# Pure_VCA.net
KiCad netlist of a schematic drawn in EAGLE
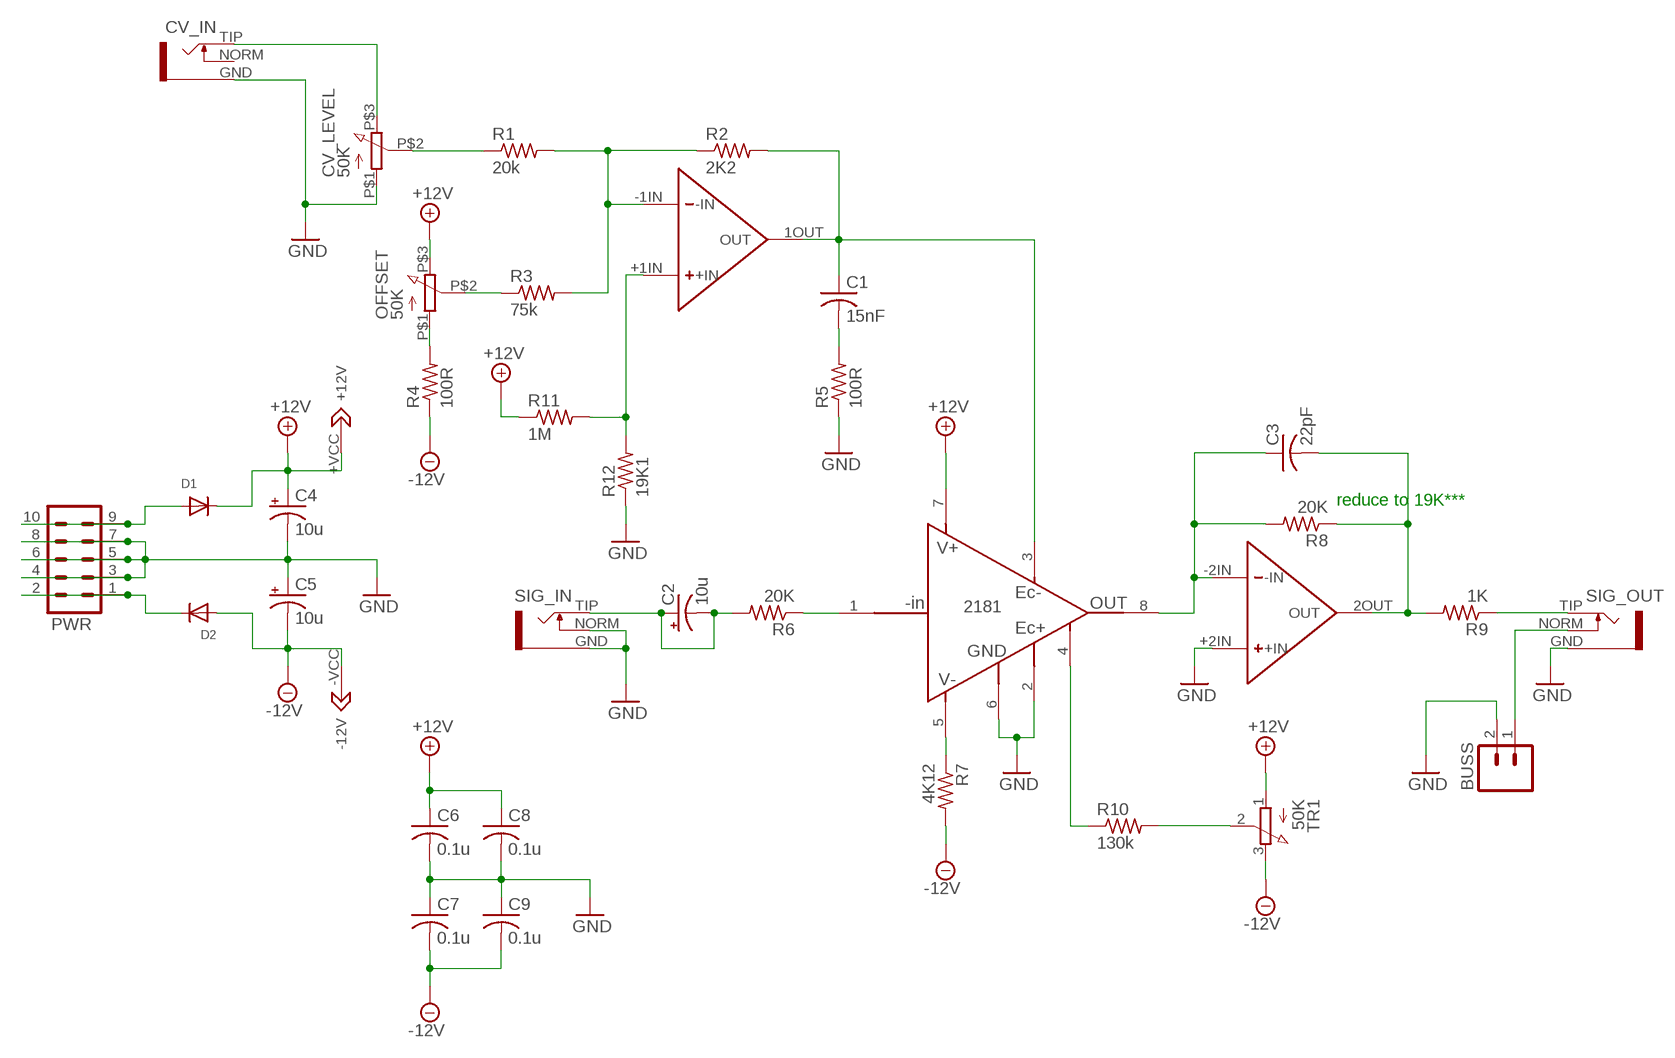
[diagram p0: schematic, sheet 1]

(export (version "E")
  (design (tool "Eeschema 10.0.6"))
  (components
    (comp (ref "BUSS")
      (value "M02PTH")
      (footprint "eagle-import:1X02")
      (libsource (lib "eagle-import") (part "M02PTH"))
    )
    (comp (ref "C1")
      (value "15nF")
      (footprint "eagle-import:C0805K")
      (libsource (lib "eagle-import") (part "C-USC0805K"))
    )
    (comp (ref "C2")
      (value "10u")
      (footprint "eagle-import:153CLV-0505")
      (libsource (lib "eagle-import") (part "CPOL-US153CLV-0505"))
    )
    (comp (ref "C3")
      (value "22pF")
      (footprint "eagle-import:C0805K")
      (libsource (lib "eagle-import") (part "C-USC0805K"))
    )
    (comp (ref "C4")
      (value "10u")
      (footprint "eagle-import:153CLV-0505")
      (libsource (lib "eagle-import") (part "CPOL-US153CLV-0505"))
    )
    (comp (ref "C5")
      (value "10u")
      (footprint "eagle-import:153CLV-0505")
      (libsource (lib "eagle-import") (part "CPOL-US153CLV-0505"))
    )
    (comp (ref "C6")
      (value "0.1u")
      (footprint "eagle-import:C0805K")
      (libsource (lib "eagle-import") (part "C-USC0805K"))
    )
    (comp (ref "C7")
      (value "0.1u")
      (footprint "eagle-import:C0805K")
      (libsource (lib "eagle-import") (part "C-USC0805K"))
    )
    (comp (ref "C8")
      (value "0.1u")
      (footprint "eagle-import:C0805K")
      (libsource (lib "eagle-import") (part "C-USC0805K"))
    )
    (comp (ref "C9")
      (value "0.1u")
      (footprint "eagle-import:C0805K")
      (libsource (lib "eagle-import") (part "C-USC0805K"))
    )
    (comp (ref "CV_IN")
      (value "S_JACK")
      (footprint "eagle-import:S_JACK")
      (libsource (lib "eagle-import") (part "S_JACK"))
    )
    (comp (ref "CV_LEVEL")
      (value "50K")
      (footprint "eagle-import:Q-POT")
      (libsource (lib "eagle-import") (part "Q-POT"))
    )
    (comp (ref "D1")
      (value "DIODESMA")
      (footprint "eagle-import:SMADIODE")
      (libsource (lib "eagle-import") (part "DIODESMA"))
    )
    (comp (ref "D2")
      (value "DIODESMA")
      (footprint "eagle-import:SMADIODE")
      (libsource (lib "eagle-import") (part "DIODESMA"))
    )
    (comp (ref "OFFSET")
      (value "50K")
      (footprint "eagle-import:Q-POT")
      (libsource (lib "eagle-import") (part "Q-POT"))
    )
    (comp (ref "PWR")
      (value "M05X2SHD")
      (footprint "eagle-import:2X5-SHROUDED")
      (libsource (lib "eagle-import") (part "M05X2SHD"))
    )
    (comp (ref "R1")
      (value "20k")
      (footprint "eagle-import:R0805")
      (libsource (lib "eagle-import") (part "R-US_R0805"))
    )
    (comp (ref "R2")
      (value "2K2")
      (footprint "eagle-import:R0805")
      (libsource (lib "eagle-import") (part "R-US_R0805"))
    )
    (comp (ref "R3")
      (value "75k")
      (footprint "eagle-import:R0805")
      (libsource (lib "eagle-import") (part "R-US_R0805"))
    )
    (comp (ref "R4")
      (value "100R")
      (footprint "eagle-import:R0805")
      (libsource (lib "eagle-import") (part "R-US_R0805"))
    )
    (comp (ref "R5")
      (value "100R")
      (footprint "eagle-import:R0805")
      (libsource (lib "eagle-import") (part "R-US_R0805"))
    )
    (comp (ref "R6")
      (value "20K")
      (footprint "eagle-import:R0805")
      (libsource (lib "eagle-import") (part "R-US_R0805"))
    )
    (comp (ref "R7")
      (value "4K12")
      (footprint "eagle-import:R0805")
      (libsource (lib "eagle-import") (part "R-US_R0805"))
    )
    (comp (ref "R8")
      (value "20K")
      (footprint "eagle-import:R0805")
      (libsource (lib "eagle-import") (part "R-US_R0805"))
    )
    (comp (ref "R9")
      (value "1K")
      (footprint "eagle-import:R0805")
      (libsource (lib "eagle-import") (part "R-US_R0805"))
    )
    (comp (ref "R10")
      (value "130k")
      (footprint "eagle-import:R0805")
      (libsource (lib "eagle-import") (part "R-US_R0805"))
    )
    (comp (ref "R11")
      (value "1M")
      (footprint "eagle-import:R0805")
      (libsource (lib "eagle-import") (part "R-US_R0805"))
    )
    (comp (ref "R12")
      (value "19K1")
      (footprint "eagle-import:R0805")
      (libsource (lib "eagle-import") (part "R-US_R0805"))
    )
    (comp (ref "SIG_IN")
      (value "S_JACK")
      (footprint "eagle-import:S_JACK")
      (libsource (lib "eagle-import") (part "S_JACK"))
    )
    (comp (ref "SIG_OUT")
      (value "S_JACK")
      (footprint "eagle-import:S_JACK")
      (libsource (lib "eagle-import") (part "S_JACK"))
    )
    (comp (ref "TR1")
      (value "50K")
      (footprint "eagle-import:TRIM_3269W")
      (libsource (lib "eagle-import") (part "TRIM_3269W"))
    )
    (comp (ref "U1")
      (value "DUAL_OPAMP")
      (footprint "eagle-import:DUAL_OPAMP")
      (libsource (lib "eagle-import") (part "DUAL_OPAMP"))
    )
    (comp (ref "U2")
      (value "THAT_2181_SMD")
      (footprint "eagle-import:SOIC--8")
      (libsource (lib "eagle-import") (part "THAT_2181_SMD"))
    )
  )
  (nets
    (net (code "1") (name "+12V") (class "Default")
      (node (ref "C4") (pin "+") (pinfunction "+_+") (pintype "passive"))
      (node (ref "C6") (pin "1") (pinfunction "1_1") (pintype "passive"))
      (node (ref "C8") (pin "1") (pinfunction "1_1") (pintype "passive"))
      (node (ref "D1") (pin "C") (pinfunction "C_C") (pintype "passive"))
      (node (ref "OFFSET") (pin "P$3") (pinfunction "3_P$3") (pintype "passive"))
      (node (ref "R11") (pin "1") (pinfunction "1_1") (pintype "passive"))
      (node (ref "TR1") (pin "1") (pinfunction "1_1") (pintype "passive"))
      (node (ref "U1") (pin "+VCC") (pinfunction "+12V_+VCC") (pintype "bidirectional"))
      (node (ref "U2") (pin "7") (pinfunction "V+_7") (pintype "bidirectional"))
    )
    (net (code "2") (name "-12V") (class "Default")
      (node (ref "C5") (pin "-") (pinfunction "-_-") (pintype "passive"))
      (node (ref "C7") (pin "2") (pinfunction "2_2") (pintype "passive"))
      (node (ref "C9") (pin "2") (pinfunction "2_2") (pintype "passive"))
      (node (ref "D2") (pin "A") (pinfunction "A_A") (pintype "passive"))
      (node (ref "R4") (pin "1") (pinfunction "1_1") (pintype "passive"))
      (node (ref "R7") (pin "2") (pinfunction "2_2") (pintype "passive"))
      (node (ref "TR1") (pin "3") (pinfunction "3_3") (pintype "passive"))
      (node (ref "U1") (pin "-VCC") (pinfunction "-12V_-VCC") (pintype "bidirectional"))
    )
    (net (code "3") (name "GND") (class "Default")
      (node (ref "BUSS") (pin "2") (pinfunction "2_2") (pintype "passive"))
      (node (ref "C4") (pin "-") (pinfunction "-_-") (pintype "passive"))
      (node (ref "C5") (pin "+") (pinfunction "+_+") (pintype "passive"))
      (node (ref "C6") (pin "2") (pinfunction "2_2") (pintype "passive"))
      (node (ref "C7") (pin "1") (pinfunction "1_1") (pintype "passive"))
      (node (ref "C8") (pin "2") (pinfunction "2_2") (pintype "passive"))
      (node (ref "C9") (pin "1") (pinfunction "1_1") (pintype "passive"))
      (node (ref "CV_IN") (pin "GND") (pinfunction "GND_GND") (pintype "passive"))
      (node (ref "CV_LEVEL") (pin "P$1") (pinfunction "1_P$1") (pintype "passive"))
      (node (ref "PWR") (pin "3") (pinfunction "3_3") (pintype "passive"))
      (node (ref "PWR") (pin "4") (pinfunction "4_4") (pintype "passive"))
      (node (ref "PWR") (pin "5") (pinfunction "5_5") (pintype "passive"))
      (node (ref "PWR") (pin "6") (pinfunction "6_6") (pintype "passive"))
      (node (ref "PWR") (pin "7") (pinfunction "7_7") (pintype "passive"))
      (node (ref "PWR") (pin "8") (pinfunction "8_8") (pintype "passive"))
      (node (ref "R12") (pin "1") (pinfunction "1_1") (pintype "passive"))
      (node (ref "R5") (pin "1") (pinfunction "1_1") (pintype "passive"))
      (node (ref "SIG_IN") (pin "GND") (pinfunction "GND_GND") (pintype "passive"))
      (node (ref "SIG_IN") (pin "NORM") (pinfunction "NORM_NORM") (pintype "passive"))
      (node (ref "SIG_OUT") (pin "GND") (pinfunction "GND_GND") (pintype "passive"))
      (node (ref "U1") (pin "+2IN") (pinfunction "+IN_+2IN") (pintype "bidirectional"))
      (node (ref "U2") (pin "2") (pinfunction "EC+_2") (pintype "bidirectional"))
      (node (ref "U2") (pin "6") (pinfunction "GND_6") (pintype "bidirectional"))
    )
    (net (code "4") (name "Net-(BUSS-Pad1)") (class "Default")
      (node (ref "BUSS") (pin "1") (pinfunction "1_1") (pintype "passive"))
      (node (ref "SIG_OUT") (pin "NORM") (pinfunction "NORM_NORM") (pintype "passive"))
    )
    (net (code "5") (name "Net-(C1-Pad2)") (class "Default")
      (node (ref "C1") (pin "2") (pinfunction "2_2") (pintype "passive"))
      (node (ref "R5") (pin "2") (pinfunction "2_2") (pintype "passive"))
    )
    (net (code "6") (name "Net-(C2-Pad+)") (class "Default")
      (node (ref "C2") (pin "+") (pinfunction "+_+") (pintype "passive"))
      (node (ref "C2") (pin "-") (pinfunction "-_-") (pintype "passive"))
      (node (ref "R6") (pin "2") (pinfunction "2_2") (pintype "passive"))
      (node (ref "SIG_IN") (pin "TIP") (pinfunction "TIP_TIP") (pintype "passive"))
    )
    (net (code "7") (name "Net-(CV_LEVEL-2)") (class "Default")
      (node (ref "CV_LEVEL") (pin "P$2") (pinfunction "2_P$2") (pintype "passive"))
      (node (ref "R1") (pin "1") (pinfunction "1_1") (pintype "passive"))
    )
    (net (code "8") (name "Net-(CV_LEVEL-3)") (class "Default")
      (node (ref "CV_IN") (pin "TIP") (pinfunction "TIP_TIP") (pintype "passive"))
      (node (ref "CV_LEVEL") (pin "P$3") (pinfunction "3_P$3") (pintype "passive"))
    )
    (net (code "9") (name "Net-(D1-PadA)") (class "Default")
      (node (ref "D1") (pin "A") (pinfunction "A_A") (pintype "passive"))
      (node (ref "PWR") (pin "10") (pinfunction "10_10") (pintype "passive"))
      (node (ref "PWR") (pin "9") (pinfunction "9_9") (pintype "passive"))
    )
    (net (code "10") (name "Net-(D2-PadC)") (class "Default")
      (node (ref "D2") (pin "C") (pinfunction "C_C") (pintype "passive"))
      (node (ref "PWR") (pin "1") (pinfunction "1_1") (pintype "passive"))
      (node (ref "PWR") (pin "2") (pinfunction "2_2") (pintype "passive"))
    )
    (net (code "11") (name "Net-(OFFSET-1)") (class "Default")
      (node (ref "OFFSET") (pin "P$1") (pinfunction "1_P$1") (pintype "passive"))
      (node (ref "R4") (pin "2") (pinfunction "2_2") (pintype "passive"))
    )
    (net (code "12") (name "Net-(OFFSET-2)") (class "Default")
      (node (ref "OFFSET") (pin "P$2") (pinfunction "2_P$2") (pintype "passive"))
      (node (ref "R3") (pin "1") (pinfunction "1_1") (pintype "passive"))
    )
    (net (code "13") (name "Net-(R9-Pad1)") (class "Default")
      (node (ref "R9") (pin "1") (pinfunction "1_1") (pintype "passive"))
      (node (ref "SIG_OUT") (pin "TIP") (pinfunction "TIP_TIP") (pintype "passive"))
    )
    (net (code "14") (name "Net-(R10-Pad2)") (class "Default")
      (node (ref "R10") (pin "2") (pinfunction "2_2") (pintype "passive"))
      (node (ref "TR1") (pin "2") (pinfunction "2_2") (pintype "passive"))
    )
    (net (code "15") (name "Net-(U1A-+IN)") (class "Default")
      (node (ref "R11") (pin "2") (pinfunction "2_2") (pintype "passive"))
      (node (ref "R12") (pin "2") (pinfunction "2_2") (pintype "passive"))
      (node (ref "U1") (pin "+1IN") (pinfunction "+IN_+1IN") (pintype "bidirectional"))
    )
    (net (code "16") (name "Net-(U1A--IN)") (class "Default")
      (node (ref "R1") (pin "2") (pinfunction "2_2") (pintype "passive"))
      (node (ref "R2") (pin "1") (pinfunction "1_1") (pintype "passive"))
      (node (ref "R3") (pin "2") (pinfunction "2_2") (pintype "passive"))
      (node (ref "U1") (pin "-1IN") (pinfunction "-IN_-1IN") (pintype "bidirectional"))
    )
    (net (code "17") (name "Net-(U1A-OUT)") (class "Default")
      (node (ref "C1") (pin "1") (pinfunction "1_1") (pintype "passive"))
      (node (ref "R2") (pin "2") (pinfunction "2_2") (pintype "passive"))
      (node (ref "U1") (pin "1OUT") (pinfunction "OUT_1OUT") (pintype "bidirectional"))
      (node (ref "U2") (pin "3") (pinfunction "EC-_3") (pintype "bidirectional"))
    )
    (net (code "18") (name "Net-(U1B--IN)") (class "Default")
      (node (ref "C3") (pin "1") (pinfunction "1_1") (pintype "passive"))
      (node (ref "R8") (pin "2") (pinfunction "2_2") (pintype "passive"))
      (node (ref "U1") (pin "-2IN") (pinfunction "-IN_-2IN") (pintype "bidirectional"))
      (node (ref "U2") (pin "8") (pinfunction "OUT_8") (pintype "bidirectional"))
    )
    (net (code "19") (name "Net-(U1B-OUT)") (class "Default")
      (node (ref "C3") (pin "2") (pinfunction "2_2") (pintype "passive"))
      (node (ref "R8") (pin "1") (pinfunction "1_1") (pintype "passive"))
      (node (ref "R9") (pin "2") (pinfunction "2_2") (pintype "passive"))
      (node (ref "U1") (pin "2OUT") (pinfunction "OUT_2OUT") (pintype "bidirectional"))
    )
    (net (code "20") (name "Net-(U2--IN)") (class "Default")
      (node (ref "R6") (pin "1") (pinfunction "1_1") (pintype "passive"))
      (node (ref "U2") (pin "1") (pinfunction "-IN_1") (pintype "bidirectional"))
    )
    (net (code "21") (name "Net-(U2-SYM)") (class "Default")
      (node (ref "R10") (pin "1") (pinfunction "1_1") (pintype "passive"))
      (node (ref "U2") (pin "4") (pinfunction "SYM_4") (pintype "bidirectional"))
    )
    (net (code "22") (name "Net-(U2-V-)") (class "Default")
      (node (ref "R7") (pin "1") (pinfunction "1_1") (pintype "passive"))
      (node (ref "U2") (pin "5") (pinfunction "V-_5") (pintype "bidirectional"))
    )
    (net (code "23") (name "unconnected-(CV_IN-PadNORM)") (class "Default")
      (node (ref "CV_IN") (pin "NORM") (pinfunction "NORM_NORM") (pintype "passive"))
    )
  )
)
